# wiz55stm32.net
KiCad netlist of a schematic drawn in Altium Designer
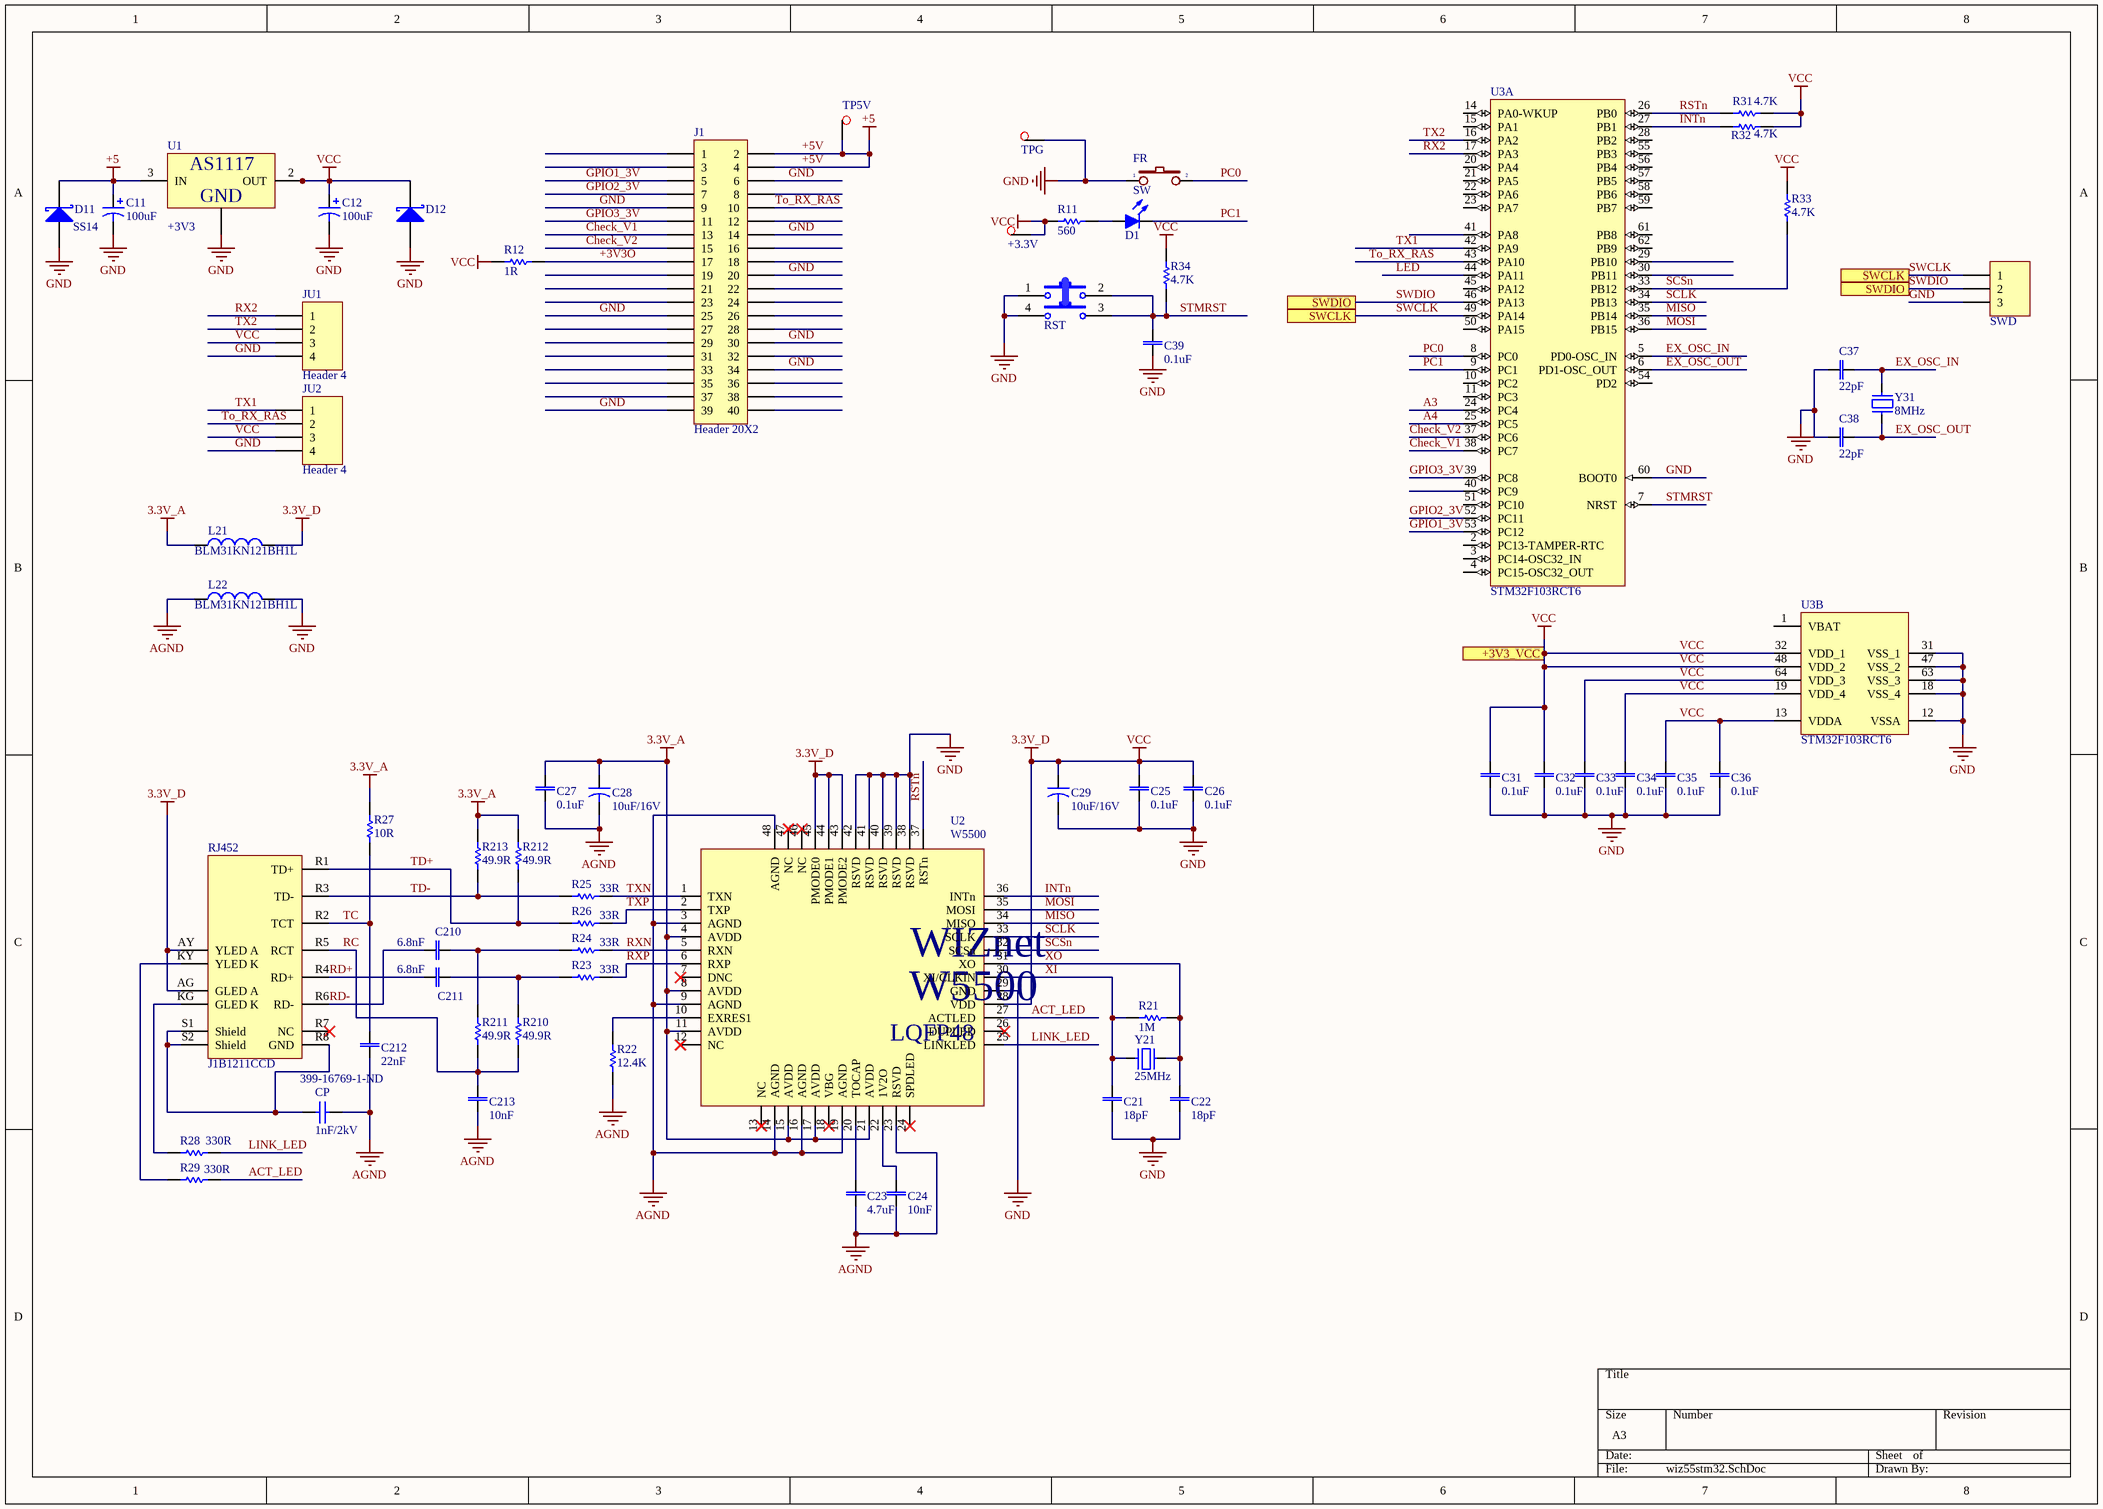
[diagram p0: wiz55stm32.SchDoc]

(export (version "E")
  (design (tool "Eeschema 10.0.6"))
  (components
    (comp (ref "+3.3V") (value "TP") (footprint "swatpcblib:TP2") (libsource (lib "swatpcblib") (part "TP")))
    (comp (ref "C11")
      (value "100uF")
      (footprint "CAP 3.8mm")
      (fields (field (name "Comment") "Cap"))
      (libsource (lib "swatpcblib") (part "Cap"))
    )
    (comp (ref "C12")
      (value "100uF")
      (footprint "CAP 3.8mm")
      (fields (field (name "Comment") "Cap"))
      (libsource (lib "swatpcblib") (part "Cap"))
    )
    (comp (ref "C21")
      (value "18pF")
      (footprint "swatpcblib:CAP 0805")
      (description "Capacitor non polarized")
      (fields (field (name "Comment") "Tụ điện dán 080518pF"))
      (libsource (lib "swatpcblib") (part "CAP NP"))
    )
    (comp (ref "C22")
      (value "18pF")
      (footprint "swatpcblib:CAP 0805")
      (description "Capacitor non polarized")
      (fields (field (name "Comment") "Tụ điện dán 080518pF"))
      (libsource (lib "swatpcblib") (part "CAP NP"))
    )
    (comp (ref "C23")
      (value "4.7uF")
      (footprint "swatpcblib:CAP 0805")
      (description "Capacitor non polarized")
      (fields (field (name "Comment") "Tụ điện dán 08054.7uF"))
      (libsource (lib "swatpcblib") (part "CAP NP"))
    )
    (comp (ref "C24")
      (value "10nF")
      (footprint "swatpcblib:CAP 0805")
      (description "Capacitor non polarized")
      (fields (field (name "Comment") "Tụ điện dán 080510nF"))
      (libsource (lib "swatpcblib") (part "CAP NP"))
    )
    (comp (ref "C25")
      (value "0.1uF")
      (footprint "swatpcblib:CAP 0805")
      (description "Capacitor non polarized")
      (fields (field (name "Comment") "Tụ điện dán 08050.1uF"))
      (libsource (lib "swatpcblib") (part "CAP NP"))
    )
    (comp (ref "C26")
      (value "0.1uF")
      (footprint "swatpcblib:CAP 0805")
      (description "Capacitor non polarized")
      (fields (field (name "Comment") "Tụ điện dán 08050.1uF"))
      (libsource (lib "swatpcblib") (part "CAP NP"))
    )
    (comp (ref "C27")
      (value "0.1uF")
      (footprint "swatpcblib:CAP 0805")
      (description "Capacitor non polarized")
      (fields (field (name "Comment") "Tụ điện dán 08050.1uF"))
      (libsource (lib "swatpcblib") (part "CAP NP"))
    )
    (comp (ref "C28")
      (value "10uF/16V")
      (footprint "CAP-A Size")
      (description "Tantla CAP A Size EIA/IECQ 3216")
      (libsource (lib "Scott_lib") (part "CAP-A Size"))
    )
    (comp (ref "C29")
      (value "10uF/16V")
      (footprint "CAP-A Size")
      (description "Tantla CAP A Size EIA/IECQ 3216")
      (libsource (lib "Scott_lib") (part "CAP-A Size"))
    )
    (comp (ref "C31")
      (value "0.1uF")
      (footprint "swatpcblib:CAP 0805")
      (description "Capacitor non polarized")
      (fields (field (name "Comment") "Tụ điện dán 08050.1uF"))
      (libsource (lib "swatpcblib") (part "CAP NP"))
    )
    (comp (ref "C32")
      (value "0.1uF")
      (footprint "swatpcblib:CAP 0805")
      (description "Capacitor non polarized")
      (fields (field (name "Comment") "Tụ điện dán 08050.1uF"))
      (libsource (lib "swatpcblib") (part "CAP NP"))
    )
    (comp (ref "C33")
      (value "0.1uF")
      (footprint "swatpcblib:CAP 0805")
      (description "Capacitor non polarized")
      (fields (field (name "Comment") "Tụ điện dán 08050.1uF"))
      (libsource (lib "swatpcblib") (part "CAP NP"))
    )
    (comp (ref "C34")
      (value "0.1uF")
      (footprint "swatpcblib:CAP 0805")
      (description "Capacitor non polarized")
      (fields (field (name "Comment") "Tụ điện dán 08050.1uF"))
      (libsource (lib "swatpcblib") (part "CAP NP"))
    )
    (comp (ref "C35")
      (value "0.1uF")
      (footprint "swatpcblib:CAP 0805")
      (description "Capacitor non polarized")
      (fields (field (name "Comment") "Tụ điện dán 08050.1uF"))
      (libsource (lib "swatpcblib") (part "CAP NP"))
    )
    (comp (ref "C36")
      (value "0.1uF")
      (footprint "swatpcblib:CAP 0805")
      (description "Capacitor non polarized")
      (fields (field (name "Comment") "Tụ điện dán 08050.1uF"))
      (libsource (lib "swatpcblib") (part "CAP NP"))
    )
    (comp (ref "C37")
      (value "22pF")
      (footprint "swatpcblib:CAP 0805")
      (description "Capacitor non polarized")
      (fields (field (name "Comment") "Tụ điện dán 080522pF"))
      (libsource (lib "swatpcblib") (part "CAP NP"))
    )
    (comp (ref "C38")
      (value "22pF")
      (footprint "swatpcblib:CAP 0805")
      (description "Capacitor non polarized")
      (fields (field (name "Comment") "Tụ điện dán 080522pF"))
      (libsource (lib "swatpcblib") (part "CAP NP"))
    )
    (comp (ref "C39")
      (value "0.1uF")
      (footprint "swatpcblib:CAP 0805")
      (description "Capacitor non polarized")
      (fields (field (name "Comment") "Tụ điện dán 08050.1uF"))
      (libsource (lib "swatpcblib") (part "CAP NP"))
    )
    (comp (ref "C210")
      (value "6.8nF")
      (footprint "swatpcblib:CAP 0805")
      (description "Capacitor non polarized")
      (fields (field (name "Comment") "Tụ điện dán 08056.8nF"))
      (libsource (lib "swatpcblib") (part "CAP NP"))
    )
    (comp (ref "C211")
      (value "6.8nF")
      (footprint "swatpcblib:CAP 0805")
      (description "Capacitor non polarized")
      (fields (field (name "Comment") "Tụ điện dán 08056.8nF"))
      (libsource (lib "swatpcblib") (part "CAP NP"))
    )
    (comp (ref "C212")
      (value "22nF")
      (footprint "swatpcblib:CAP 0805")
      (description "Capacitor non polarized")
      (fields (field (name "Comment") "Tụ điện dán 080522nF"))
      (libsource (lib "swatpcblib") (part "CAP NP"))
    )
    (comp (ref "C213")
      (value "10nF")
      (footprint "swatpcblib:CAP 0805")
      (description "Capacitor non polarized")
      (fields (field (name "Comment") "Tụ điện dán 080510nF"))
      (libsource (lib "swatpcblib") (part "CAP NP"))
    )
    (comp (ref "CP")
      (value "1nF/2kV")
      (footprint "CAP-1808")
      (description "Ceramic CAP 1808(4520)")
      (fields (field (name "SUPPLIER PART NUMBER 1") "399-16769-1-ND") (field (name "TOLERANCE") "20%"))
      (libsource (lib "Scott_lib") (part "CAP-1808"))
    )
    (comp (ref "D1") (value "Led") (footprint "LED 5mm Green") (libsource (lib "swatpcblib") (part "Led")))
    (comp (ref "D11")
      (value "SS14")
      (footprint "PBL - SMD Packages:DO-214AC")
      (description "Schottky Diodes Through Hole 3 A 40 V Schottky Diodes, DO-201AD, SB340 ,MBR340")
      (fields (field (name "Comment") "Đi ốt dánSS14"))
      (libsource (lib "swatpcblib") (part "Diodes Schottky"))
    )
    (comp (ref "D12")
      (value "Đi ốt dánPN:CPDH3V3UP")
      (footprint "swatpcblib:DO-35")
      (description "Zener 3.3V/1W")
      (libsource (lib "swatpcblib") (part "Diodes Schottky"))
    )
    (comp (ref "FR")
      (value "SW")
      (footprint "heromap:SW2-D1")
      (description "Switch button 2 pin")
      (libsource (lib "heromap") (part "SW2"))
    )
    (comp (ref "J1")
      (value "Header 20X2")
      (footprint "HDR2X20")
      (description "Header, 20-Pin, Dual row")
      (fields (field (name "PUBLISHER") "Altium Limited"))
      (libsource (lib "Miscellaneous Connectors") (part "Header 20X2"))
    )
    (comp (ref "JU1")
      (value "Header 4")
      (footprint "heromap:HDR1X4")
      (description "Header, 4-Pin")
      (fields (field (name "PUBLISHER") "Altium Limited"))
      (libsource (lib "heromap") (part "Header 4"))
    )
    (comp (ref "JU2")
      (value "Header 4")
      (footprint "heromap:HDR1X4")
      (description "Header, 4-Pin")
      (fields (field (name "PUBLISHER") "Altium Limited"))
      (libsource (lib "heromap") (part "Header 4"))
    )
    (comp (ref "L21")
      (value "BLM31KN121BH1L")
      (footprint "swatpcblib:SMD 1206")
      (description "Ferrite Beads 1206 120ohms 4A AEC-Q200")
      (libsource (lib "Scott_lib") (part "IND-0603"))
    )
    (comp (ref "L22")
      (value "BLM31KN121BH1L")
      (footprint "swatpcblib:SMD 1206")
      (description "Ferrite Beads 1206 120ohms 4A AEC-Q200")
      (libsource (lib "Scott_lib") (part "IND-0603"))
    )
    (comp (ref "R11")
      (value "560")
      (footprint "swatpcblib:RES 0805")
      (description "Resistor")
      (fields (field (name "Comment") "Điện trở dán 0603560"))
      (libsource (lib "swatpcblib") (part "Res"))
    )
    (comp (ref "R12")
      (value "1R")
      (footprint "swatpcblib:RES 0805")
      (description "Resistor")
      (fields (field (name "Comment") "Điện trở dán 08051R"))
      (libsource (lib "swatpcblib") (part "Res"))
    )
    (comp (ref "R21")
      (value "1M")
      (footprint "swatpcblib:RES 0805")
      (description "Resistor")
      (fields (field (name "Comment") "Điện trở dán 08051M"))
      (libsource (lib "swatpcblib") (part "Res"))
    )
    (comp (ref "R22")
      (value "12.4K")
      (footprint "swatpcblib:RES 0805")
      (description "Resistor")
      (fields (field (name "Comment") "Điện trở dán 080512.4K"))
      (libsource (lib "swatpcblib") (part "Res"))
    )
    (comp (ref "R23")
      (value "33R")
      (footprint "swatpcblib:RES 0805")
      (description "Resistor")
      (fields (field (name "Comment") "Điện trở dán 080533R"))
      (libsource (lib "swatpcblib") (part "Res"))
    )
    (comp (ref "R24")
      (value "33R")
      (footprint "swatpcblib:RES 0805")
      (description "Resistor")
      (fields (field (name "Comment") "Điện trở dán 080533R"))
      (libsource (lib "swatpcblib") (part "Res"))
    )
    (comp (ref "R25")
      (value "33R")
      (footprint "swatpcblib:RES 0805")
      (description "Resistor")
      (fields (field (name "Comment") "Điện trở dán 080533R"))
      (libsource (lib "swatpcblib") (part "Res"))
    )
    (comp (ref "R26")
      (value "33R")
      (footprint "swatpcblib:RES 0805")
      (description "Resistor")
      (fields (field (name "Comment") "Điện trở dán 080533R"))
      (libsource (lib "swatpcblib") (part "Res"))
    )
    (comp (ref "R27")
      (value "10R")
      (footprint "swatpcblib:RES 0805")
      (description "Resistor")
      (fields (field (name "Comment") "Điện trở dán 080510R"))
      (libsource (lib "swatpcblib") (part "Res"))
    )
    (comp (ref "R28")
      (value "330R")
      (footprint "swatpcblib:RES 0805")
      (description "Resistor")
      (fields (field (name "Comment") "Điện trở dán 0805330R"))
      (libsource (lib "swatpcblib") (part "Res"))
    )
    (comp (ref "R29")
      (value "330R")
      (footprint "swatpcblib:RES 0805")
      (description "Resistor")
      (fields (field (name "Comment") "Điện trở dán 0805330R"))
      (libsource (lib "swatpcblib") (part "Res"))
    )
    (comp (ref "R31")
      (value "4.7K")
      (footprint "swatpcblib:RES 0805")
      (description "Resistor")
      (fields (field (name "Comment") "Điện trở dán 08054.7K"))
      (libsource (lib "swatpcblib") (part "Res"))
    )
    (comp (ref "R32")
      (value "4.7K")
      (footprint "swatpcblib:RES 0805")
      (description "Resistor")
      (fields (field (name "Comment") "Điện trở dán 08054.7K"))
      (libsource (lib "swatpcblib") (part "Res"))
    )
    (comp (ref "R33")
      (value "4.7K")
      (footprint "swatpcblib:RES 0805")
      (description "Resistor")
      (fields (field (name "Comment") "Điện trở dán 08054.7K"))
      (libsource (lib "swatpcblib") (part "Res"))
    )
    (comp (ref "R34")
      (value "4.7K")
      (footprint "swatpcblib:RES 0805")
      (description "Resistor")
      (fields (field (name "Comment") "Điện trở dán 08054.7K"))
      (libsource (lib "swatpcblib") (part "Res"))
    )
    (comp (ref "R210")
      (value "49.9R")
      (footprint "swatpcblib:RES 0805")
      (description "Resistor")
      (fields (field (name "Comment") "Điện trở dán 080549.9R"))
      (libsource (lib "swatpcblib") (part "Res"))
    )
    (comp (ref "R211")
      (value "49.9R")
      (footprint "swatpcblib:RES 0805")
      (description "Resistor")
      (fields (field (name "Comment") "Điện trở dán 080549.9R"))
      (libsource (lib "swatpcblib") (part "Res"))
    )
    (comp (ref "R212")
      (value "49.9R")
      (footprint "swatpcblib:RES 0805")
      (description "Resistor")
      (fields (field (name "Comment") "Điện trở dán 080549.9R"))
      (libsource (lib "swatpcblib") (part "Res"))
    )
    (comp (ref "R213")
      (value "49.9R")
      (footprint "swatpcblib:RES 0805")
      (description "Resistor")
      (fields (field (name "Comment") "Điện trở dán 080549.9R"))
      (libsource (lib "swatpcblib") (part "Res"))
    )
    (comp (ref "RJ452")
      (value "J1B1211CCD")
      (footprint "swatpcblib:J1B1211CCD")
      (libsource (lib "WIZ850io_SCH_V100") (part "BS-R250210"))
    )
    (comp (ref "RST")
      (value "Nút bấm 4 chân cắm12x12x6mm")
      (footprint "SW")
      (libsource (lib "swatpcblib") (part "SW-4P-Small"))
    )
    (comp (ref "SWD")
      (value "Header 3")
      (footprint "heromap:HDR1X3")
      (description "Header, 3-Pin")
      (fields (field (name "PUBLISHER") "Altium Limited"))
      (libsource (lib "heromap") (part "Header 3"))
    )
    (comp (ref "TP5V") (value "TP") (footprint "swatpcblib:TP2") (libsource (lib "swatpcblib") (part "TP")))
    (comp (ref "TPG") (value "TP") (footprint "swatpcblib:TP2") (libsource (lib "swatpcblib") (part "TP")))
    (comp (ref "U1")
      (value "IC nguồn AS1117 dán+3V3")
      (footprint "SOT223-4N")
      (fields (field (name "VL") "+3V3"))
      (libsource (lib "swatpcblib") (part "AS1117"))
    )
    (comp (ref "U2")
      (value "W5500")
      (footprint "WIZnet W5500")
      (description "WIZnet W5500")
      (libsource (lib "WIZnet Open-source Hardware Library V1.0") (part "W5500"))
    )
    (comp (ref "U3")
      (value "STM32F103RCT6")
      (footprint "LQFP64_Tuan")
      (libsource (lib "STMicroelectronics STM32 F1") (part "STM32F103RCT6"))
    )
    (comp (ref "Y21") (value "25MHz") (footprint "XT2") (libsource (lib "swatpcblib") (part "Crystal")))
    (comp (ref "Y31") (value "8MHz") (footprint "XT2") (libsource (lib "Tuan") (part "Crystal")))
  )
  (nets
    (net (code "1") (name "+5") (class "Default")
      (node (ref "C11") (pin "1") (pinfunction "1_1") (pintype "passive"))
      (node (ref "D11") (pin "K") (pinfunction "K_K") (pintype "passive"))
      (node (ref "J1") (pin "2") (pinfunction "2_2") (pintype "passive"))
      (node (ref "J1") (pin "4") (pinfunction "4_4") (pintype "passive"))
      (node (ref "TP5V") (pin "1") (pinfunction "1_1") (pintype "passive"))
      (node (ref "U1") (pin "3") (pinfunction "IN_3") (pintype "power_in"))
    )
    (net (code "2") (name "/+3V3O") (class "Default")
      (node (ref "J1") (pin "17") (pinfunction "17_17") (pintype "passive"))
      (node (ref "R12") (pin "2") (pinfunction "2_2") (pintype "passive"))
    )
    (net (code "3") (name "/A3") (class "Default")
      (node (ref "U3") (pin "24") (pinfunction "PC4_24") (pintype "bidirectional"))
    )
    (net (code "4") (name "/A4") (class "Default")
      (node (ref "U3") (pin "25") (pinfunction "PC5_25") (pintype "bidirectional"))
    )
    (net (code "5") (name "/ACT_LED") (class "Default")
      (node (ref "R29") (pin "2") (pinfunction "2_2") (pintype "passive"))
      (node (ref "U2") (pin "27") (pinfunction "ACTLED_27") (pintype "passive"))
    )
    (net (code "6") (name "/Check_V1") (class "Default")
      (node (ref "J1") (pin "13") (pinfunction "13_13") (pintype "passive"))
      (node (ref "U3") (pin "38") (pinfunction "PC7_38") (pintype "bidirectional"))
    )
    (net (code "7") (name "/Check_V2") (class "Default")
      (node (ref "J1") (pin "15") (pinfunction "15_15") (pintype "passive"))
      (node (ref "U3") (pin "37") (pinfunction "PC6_37") (pintype "bidirectional"))
    )
    (net (code "8") (name "/EX_OSC_IN") (class "Default")
      (node (ref "C37") (pin "1") (pinfunction "1_1") (pintype "passive"))
      (node (ref "U3") (pin "5") (pinfunction "PD0-OSC_IN_5") (pintype "bidirectional"))
      (node (ref "Y31") (pin "2") (pinfunction "2_2") (pintype "passive"))
    )
    (net (code "9") (name "/EX_OSC_OUT") (class "Default")
      (node (ref "C38") (pin "1") (pinfunction "1_1") (pintype "passive"))
      (node (ref "U3") (pin "6") (pinfunction "PD1-OSC_OUT_6") (pintype "bidirectional"))
      (node (ref "Y31") (pin "1") (pinfunction "1_1") (pintype "passive"))
    )
    (net (code "10") (name "/GPIO1_3V") (class "Default")
      (node (ref "J1") (pin "5") (pinfunction "5_5") (pintype "passive"))
      (node (ref "U3") (pin "53") (pinfunction "PC12_53") (pintype "bidirectional"))
    )
    (net (code "11") (name "/GPIO2_3V") (class "Default")
      (node (ref "J1") (pin "7") (pinfunction "7_7") (pintype "passive"))
      (node (ref "U3") (pin "52") (pinfunction "PC11_52") (pintype "bidirectional"))
    )
    (net (code "12") (name "/GPIO3_3V") (class "Default")
      (node (ref "J1") (pin "11") (pinfunction "11_11") (pintype "passive"))
      (node (ref "U3") (pin "39") (pinfunction "PC8_39") (pintype "bidirectional"))
    )
    (net (code "13") (name "/INTn") (class "Default")
      (node (ref "R32") (pin "2") (pinfunction "2_2") (pintype "passive"))
      (node (ref "U2") (pin "36") (pinfunction "INTn_36") (pintype "passive"))
      (node (ref "U3") (pin "27") (pinfunction "PB1_27") (pintype "bidirectional"))
    )
    (net (code "14") (name "/LED") (class "Default")
      (node (ref "U3") (pin "44") (pinfunction "PA11_44") (pintype "bidirectional"))
    )
    (net (code "15") (name "/LINK_LED") (class "Default")
      (node (ref "R28") (pin "2") (pinfunction "2_2") (pintype "passive"))
      (node (ref "U2") (pin "25") (pinfunction "LINKLED_25") (pintype "passive"))
    )
    (net (code "16") (name "/MISO") (class "Default")
      (node (ref "U2") (pin "34") (pinfunction "MISO_34") (pintype "passive"))
      (node (ref "U3") (pin "35") (pinfunction "PB14_35") (pintype "bidirectional"))
    )
    (net (code "17") (name "/MOSI") (class "Default")
      (node (ref "U2") (pin "35") (pinfunction "MOSI_35") (pintype "passive"))
      (node (ref "U3") (pin "36") (pinfunction "PB15_36") (pintype "bidirectional"))
    )
    (net (code "18") (name "/PC0") (class "Default")
      (node (ref "FR") (pin "2") (pinfunction "2_2") (pintype "passive"))
      (node (ref "U3") (pin "8") (pinfunction "PC0_8") (pintype "bidirectional"))
    )
    (net (code "19") (name "/PC1") (class "Default")
      (node (ref "D1") (pin "K") (pinfunction "K_K") (pintype "passive"))
      (node (ref "U3") (pin "9") (pinfunction "PC1_9") (pintype "bidirectional"))
    )
    (net (code "20") (name "/RC") (class "Default")
      (node (ref "C213") (pin "1") (pinfunction "1_1") (pintype "passive"))
      (node (ref "R210") (pin "1") (pinfunction "1_1") (pintype "passive"))
      (node (ref "R211") (pin "1") (pinfunction "1_1") (pintype "passive"))
      (node (ref "RJ452") (pin "R5") (pinfunction "RCT_R5") (pintype "passive"))
    )
    (net (code "21") (name "/RD+") (class "Default")
      (node (ref "C211") (pin "2") (pinfunction "2_2") (pintype "passive"))
      (node (ref "RJ452") (pin "R4") (pinfunction "RD+_R4") (pintype "passive"))
    )
    (net (code "22") (name "/RD-") (class "Default")
      (node (ref "C210") (pin "2") (pinfunction "2_2") (pintype "passive"))
      (node (ref "RJ452") (pin "R6") (pinfunction "RD-_R6") (pintype "passive"))
    )
    (net (code "23") (name "/RSTn") (class "Default")
      (node (ref "R31") (pin "2") (pinfunction "2_2") (pintype "passive"))
      (node (ref "U2") (pin "37") (pinfunction "RSTn_37") (pintype "passive"))
      (node (ref "U3") (pin "26") (pinfunction "PB0_26") (pintype "bidirectional"))
    )
    (net (code "24") (name "/RX2") (class "Default")
      (node (ref "JU1") (pin "1") (pinfunction "1_1") (pintype "passive"))
      (node (ref "U3") (pin "17") (pinfunction "PA3_17") (pintype "bidirectional"))
    )
    (net (code "25") (name "/RXN") (class "Default")
      (node (ref "R24") (pin "1") (pinfunction "1_1") (pintype "passive"))
      (node (ref "U2") (pin "5") (pinfunction "RXN_5") (pintype "passive"))
    )
    (net (code "26") (name "/RXP") (class "Default")
      (node (ref "R23") (pin "1") (pinfunction "1_1") (pintype "passive"))
      (node (ref "U2") (pin "6") (pinfunction "RXP_6") (pintype "passive"))
    )
    (net (code "27") (name "/SCLK") (class "Default")
      (node (ref "U2") (pin "33") (pinfunction "SCLK_33") (pintype "passive"))
      (node (ref "U3") (pin "34") (pinfunction "PB13_34") (pintype "bidirectional"))
    )
    (net (code "28") (name "/SCSn") (class "Default")
      (node (ref "R33") (pin "1") (pinfunction "1_1") (pintype "passive"))
      (node (ref "U2") (pin "32") (pinfunction "SCSn_32") (pintype "passive"))
      (node (ref "U3") (pin "33") (pinfunction "PB12_33") (pintype "bidirectional"))
    )
    (net (code "29") (name "/STMRST") (class "Default")
      (node (ref "C39") (pin "2") (pinfunction "2_2") (pintype "passive"))
      (node (ref "R34") (pin "1") (pinfunction "1_1") (pintype "passive"))
      (node (ref "RST") (pin "2") (pinfunction "2_2") (pintype "passive"))
      (node (ref "RST") (pin "3") (pinfunction "3_3") (pintype "passive"))
      (node (ref "U3") (pin "7") (pinfunction "NRST_7") (pintype "bidirectional"))
    )
    (net (code "30") (name "/SWCLK") (class "Default")
      (node (ref "SWD") (pin "1") (pinfunction "1_1") (pintype "passive"))
      (node (ref "U3") (pin "49") (pinfunction "PA14_49") (pintype "bidirectional"))
    )
    (net (code "31") (name "/SWDIO") (class "Default")
      (node (ref "SWD") (pin "2") (pinfunction "2_2") (pintype "passive"))
      (node (ref "U3") (pin "46") (pinfunction "PA13_46") (pintype "bidirectional"))
    )
    (net (code "32") (name "/TC") (class "Default")
      (node (ref "C212") (pin "1") (pinfunction "1_1") (pintype "passive"))
      (node (ref "R27") (pin "2") (pinfunction "2_2") (pintype "passive"))
      (node (ref "RJ452") (pin "R2") (pinfunction "TCT_R2") (pintype "passive"))
    )
    (net (code "33") (name "/TD+") (class "Default")
      (node (ref "R212") (pin "1") (pinfunction "1_1") (pintype "passive"))
      (node (ref "R26") (pin "2") (pinfunction "2_2") (pintype "passive"))
      (node (ref "RJ452") (pin "R1") (pinfunction "TD+_R1") (pintype "passive"))
    )
    (net (code "34") (name "/TD-") (class "Default")
      (node (ref "R213") (pin "1") (pinfunction "1_1") (pintype "passive"))
      (node (ref "R25") (pin "2") (pinfunction "2_2") (pintype "passive"))
      (node (ref "RJ452") (pin "R3") (pinfunction "TD-_R3") (pintype "passive"))
    )
    (net (code "35") (name "/TX1") (class "Default")
      (node (ref "JU2") (pin "1") (pinfunction "1_1") (pintype "passive"))
      (node (ref "U3") (pin "42") (pinfunction "PA9_42") (pintype "bidirectional"))
    )
    (net (code "36") (name "/TX2") (class "Default")
      (node (ref "JU1") (pin "2") (pinfunction "2_2") (pintype "passive"))
      (node (ref "U3") (pin "16") (pinfunction "PA2_16") (pintype "bidirectional"))
    )
    (net (code "37") (name "/TXN") (class "Default")
      (node (ref "R25") (pin "1") (pinfunction "1_1") (pintype "passive"))
      (node (ref "U2") (pin "1") (pinfunction "TXN_1") (pintype "passive"))
    )
    (net (code "38") (name "/TXP") (class "Default")
      (node (ref "R26") (pin "1") (pinfunction "1_1") (pintype "passive"))
      (node (ref "U2") (pin "2") (pinfunction "TXP_2") (pintype "passive"))
    )
    (net (code "39") (name "/To_RX_RAS") (class "Default")
      (node (ref "J1") (pin "10") (pinfunction "10_10") (pintype "passive"))
      (node (ref "JU2") (pin "2") (pinfunction "2_2") (pintype "passive"))
      (node (ref "U3") (pin "43") (pinfunction "PA10_43") (pintype "bidirectional"))
    )
    (net (code "40") (name "/XI") (class "Default")
      (node (ref "C21") (pin "2") (pinfunction "2_2") (pintype "passive"))
      (node (ref "R21") (pin "1") (pinfunction "1_1") (pintype "passive"))
      (node (ref "U2") (pin "30") (pinfunction "XI/CLKIN_30") (pintype "passive"))
      (node (ref "Y21") (pin "1") (pinfunction "1_1") (pintype "passive"))
    )
    (net (code "41") (name "/XO") (class "Default")
      (node (ref "C22") (pin "2") (pinfunction "2_2") (pintype "passive"))
      (node (ref "R21") (pin "2") (pinfunction "2_2") (pintype "passive"))
      (node (ref "U2") (pin "31") (pinfunction "XO_31") (pintype "passive"))
      (node (ref "Y21") (pin "2") (pinfunction "2_2") (pintype "passive"))
    )
    (net (code "42") (name "3.3V_A") (class "Default")
      (node (ref "C27") (pin "2") (pinfunction "2_2") (pintype "passive"))
      (node (ref "C28") (pin "1") (pinfunction "1_1") (pintype "passive"))
      (node (ref "L21") (pin "1") (pinfunction "1_1") (pintype "passive"))
      (node (ref "R212") (pin "2") (pinfunction "2_2") (pintype "passive"))
      (node (ref "R213") (pin "2") (pinfunction "2_2") (pintype "passive"))
      (node (ref "R27") (pin "1") (pinfunction "1_1") (pintype "passive"))
      (node (ref "U2") (pin "11") (pinfunction "AVDD_11") (pintype "passive"))
      (node (ref "U2") (pin "15") (pinfunction "AVDD_15") (pintype "passive"))
      (node (ref "U2") (pin "17") (pinfunction "AVDD_17") (pintype "passive"))
      (node (ref "U2") (pin "21") (pinfunction "AVDD_21") (pintype "passive"))
      (node (ref "U2") (pin "4") (pinfunction "AVDD_4") (pintype "passive"))
      (node (ref "U2") (pin "8") (pinfunction "AVDD_8") (pintype "passive"))
    )
    (net (code "43") (name "3.3V_D") (class "Default")
      (node (ref "+3.3V") (pin "1") (pinfunction "1_1") (pintype "passive"))
      (node (ref "C12") (pin "1") (pinfunction "1_1") (pintype "passive"))
      (node (ref "C25") (pin "2") (pinfunction "2_2") (pintype "passive"))
      (node (ref "C26") (pin "2") (pinfunction "2_2") (pintype "passive"))
      (node (ref "C29") (pin "1") (pinfunction "1_1") (pintype "passive"))
      (node (ref "C31") (pin "2") (pinfunction "2_2") (pintype "passive"))
      (node (ref "C32") (pin "2") (pinfunction "2_2") (pintype "passive"))
      (node (ref "C33") (pin "2") (pinfunction "2_2") (pintype "passive"))
      (node (ref "C34") (pin "2") (pinfunction "2_2") (pintype "passive"))
      (node (ref "C35") (pin "2") (pinfunction "2_2") (pintype "passive"))
      (node (ref "C36") (pin "2") (pinfunction "2_2") (pintype "passive"))
      (node (ref "D12") (pin "K") (pinfunction "K_K") (pintype "passive"))
      (node (ref "JU1") (pin "3") (pinfunction "3_3") (pintype "passive"))
      (node (ref "JU2") (pin "3") (pinfunction "3_3") (pintype "passive"))
      (node (ref "L21") (pin "2") (pinfunction "2_2") (pintype "passive"))
      (node (ref "R11") (pin "1") (pinfunction "1_1") (pintype "passive"))
      (node (ref "R12") (pin "1") (pinfunction "1_1") (pintype "passive"))
      (node (ref "R31") (pin "1") (pinfunction "1_1") (pintype "passive"))
      (node (ref "R32") (pin "1") (pinfunction "1_1") (pintype "passive"))
      (node (ref "R33") (pin "2") (pinfunction "2_2") (pintype "passive"))
      (node (ref "R34") (pin "2") (pinfunction "2_2") (pintype "passive"))
      (node (ref "RJ452") (pin "AG") (pinfunction "GLED_A_AG") (pintype "passive"))
      (node (ref "RJ452") (pin "AY") (pinfunction "YLED_A_AY") (pintype "passive"))
      (node (ref "U1") (pin "2") (pinfunction "OUT_2") (pintype "power_in"))
      (node (ref "U1") (pin "4") (pinfunction "4_4") (pintype "passive"))
      (node (ref "U2") (pin "28") (pinfunction "VDD_28") (pintype "passive"))
      (node (ref "U2") (pin "43") (pinfunction "PMODE2_43") (pintype "passive"))
      (node (ref "U2") (pin "44") (pinfunction "PMODE1_44") (pintype "passive"))
      (node (ref "U2") (pin "45") (pinfunction "PMODE0_45") (pintype "passive"))
      (node (ref "U3") (pin "13") (pinfunction "VDDA_13") (pintype "power_in"))
      (node (ref "U3") (pin "19") (pinfunction "VDD_4_19") (pintype "power_in"))
      (node (ref "U3") (pin "32") (pinfunction "VDD_1_32") (pintype "power_in"))
      (node (ref "U3") (pin "48") (pinfunction "VDD_2_48") (pintype "power_in"))
      (node (ref "U3") (pin "64") (pinfunction "VDD_3_64") (pintype "power_in"))
    )
    (net (code "44") (name "AGND") (class "Default")
      (node (ref "C212") (pin "2") (pinfunction "2_2") (pintype "passive"))
      (node (ref "C213") (pin "2") (pinfunction "2_2") (pintype "passive"))
      (node (ref "C23") (pin "1") (pinfunction "1_1") (pintype "passive"))
      (node (ref "C24") (pin "1") (pinfunction "1_1") (pintype "passive"))
      (node (ref "C27") (pin "1") (pinfunction "1_1") (pintype "passive"))
      (node (ref "C28") (pin "2") (pinfunction "2_2") (pintype "passive"))
      (node (ref "CP") (pin "1") (pinfunction "1_1") (pintype "passive"))
      (node (ref "L22") (pin "1") (pinfunction "1_1") (pintype "passive"))
      (node (ref "R22") (pin "1") (pinfunction "1_1") (pintype "passive"))
      (node (ref "U2") (pin "14") (pinfunction "AGND_14") (pintype "passive"))
      (node (ref "U2") (pin "16") (pinfunction "AGND_16") (pintype "passive"))
      (node (ref "U2") (pin "19") (pinfunction "AGND_19") (pintype "passive"))
      (node (ref "U2") (pin "23") (pinfunction "RSVD_23") (pintype "passive"))
      (node (ref "U2") (pin "3") (pinfunction "AGND_3") (pintype "passive"))
      (node (ref "U2") (pin "48") (pinfunction "AGND_48") (pintype "passive"))
      (node (ref "U2") (pin "9") (pinfunction "AGND_9") (pintype "passive"))
    )
    (net (code "45") (name "GND") (class "Default")
      (node (ref "C11") (pin "2") (pinfunction "2_2") (pintype "passive"))
      (node (ref "C12") (pin "2") (pinfunction "2_2") (pintype "passive"))
      (node (ref "C21") (pin "1") (pinfunction "1_1") (pintype "passive"))
      (node (ref "C22") (pin "1") (pinfunction "1_1") (pintype "passive"))
      (node (ref "C25") (pin "1") (pinfunction "1_1") (pintype "passive"))
      (node (ref "C26") (pin "1") (pinfunction "1_1") (pintype "passive"))
      (node (ref "C29") (pin "2") (pinfunction "2_2") (pintype "passive"))
      (node (ref "C31") (pin "1") (pinfunction "1_1") (pintype "passive"))
      (node (ref "C32") (pin "1") (pinfunction "1_1") (pintype "passive"))
      (node (ref "C33") (pin "1") (pinfunction "1_1") (pintype "passive"))
      (node (ref "C34") (pin "1") (pinfunction "1_1") (pintype "passive"))
      (node (ref "C35") (pin "1") (pinfunction "1_1") (pintype "passive"))
      (node (ref "C36") (pin "1") (pinfunction "1_1") (pintype "passive"))
      (node (ref "C37") (pin "2") (pinfunction "2_2") (pintype "passive"))
      (node (ref "C38") (pin "2") (pinfunction "2_2") (pintype "passive"))
      (node (ref "C39") (pin "1") (pinfunction "1_1") (pintype "passive"))
      (node (ref "D11") (pin "A") (pinfunction "A_A") (pintype "passive"))
      (node (ref "D12") (pin "A") (pinfunction "A_A") (pintype "passive"))
      (node (ref "FR") (pin "1") (pinfunction "1_1") (pintype "passive"))
      (node (ref "J1") (pin "14") (pinfunction "14_14") (pintype "passive"))
      (node (ref "J1") (pin "20") (pinfunction "20_20") (pintype "passive"))
      (node (ref "J1") (pin "25") (pinfunction "25_25") (pintype "passive"))
      (node (ref "J1") (pin "30") (pinfunction "30_30") (pintype "passive"))
      (node (ref "J1") (pin "34") (pinfunction "34_34") (pintype "passive"))
      (node (ref "J1") (pin "39") (pinfunction "39_39") (pintype "passive"))
      (node (ref "J1") (pin "6") (pinfunction "6_6") (pintype "passive"))
      (node (ref "J1") (pin "9") (pinfunction "9_9") (pintype "passive"))
      (node (ref "JU1") (pin "4") (pinfunction "4_4") (pintype "passive"))
      (node (ref "JU2") (pin "4") (pinfunction "4_4") (pintype "passive"))
      (node (ref "L22") (pin "2") (pinfunction "2_2") (pintype "passive"))
      (node (ref "RST") (pin "1") (pinfunction "1_1") (pintype "passive"))
      (node (ref "RST") (pin "4") (pinfunction "4_4") (pintype "passive"))
      (node (ref "SWD") (pin "3") (pinfunction "3_3") (pintype "passive"))
      (node (ref "TPG") (pin "1") (pinfunction "1_1") (pintype "passive"))
      (node (ref "U1") (pin "1") (pinfunction "GND_1") (pintype "power_in"))
      (node (ref "U2") (pin "29") (pinfunction "GND_29") (pintype "passive"))
      (node (ref "U2") (pin "38") (pinfunction "RSVD_38") (pintype "passive"))
      (node (ref "U2") (pin "39") (pinfunction "RSVD_39") (pintype "passive"))
      (node (ref "U2") (pin "40") (pinfunction "RSVD_40") (pintype "passive"))
      (node (ref "U2") (pin "41") (pinfunction "RSVD_41") (pintype "passive"))
      (node (ref "U2") (pin "42") (pinfunction "RSVD_42") (pintype "passive"))
      (node (ref "U3") (pin "12") (pinfunction "VSSA_12") (pintype "power_in"))
      (node (ref "U3") (pin "18") (pinfunction "VSS_4_18") (pintype "power_in"))
      (node (ref "U3") (pin "31") (pinfunction "VSS_1_31") (pintype "power_in"))
      (node (ref "U3") (pin "47") (pinfunction "VSS_2_47") (pintype "power_in"))
      (node (ref "U3") (pin "60") (pinfunction "BOOT0_60") (pintype "input"))
      (node (ref "U3") (pin "63") (pinfunction "VSS_3_63") (pintype "power_in"))
    )
    (net (code "46") (name "Net-(C210-Pad1)") (class "Default")
      (node (ref "C210") (pin "1") (pinfunction "1_1") (pintype "passive"))
      (node (ref "R211") (pin "2") (pinfunction "2_2") (pintype "passive"))
      (node (ref "R24") (pin "2") (pinfunction "2_2") (pintype "passive"))
    )
    (net (code "47") (name "Net-(C211-Pad1)") (class "Default")
      (node (ref "C211") (pin "1") (pinfunction "1_1") (pintype "passive"))
      (node (ref "R210") (pin "2") (pinfunction "2_2") (pintype "passive"))
      (node (ref "R23") (pin "2") (pinfunction "2_2") (pintype "passive"))
    )
    (net (code "48") (name "Net-(D1-PadA)") (class "Default")
      (node (ref "D1") (pin "A") (pinfunction "A_A") (pintype "passive"))
      (node (ref "R11") (pin "2") (pinfunction "2_2") (pintype "passive"))
    )
    (net (code "49") (name "Net-(RJ452-GLED_K)") (class "Default")
      (node (ref "R28") (pin "1") (pinfunction "1_1") (pintype "passive"))
      (node (ref "RJ452") (pin "KG") (pinfunction "GLED_K_KG") (pintype "passive"))
    )
    (net (code "50") (name "Net-(RJ452-GND)") (class "Default")
      (node (ref "CP") (pin "2") (pinfunction "2_2") (pintype "passive"))
      (node (ref "RJ452") (pin "R8") (pinfunction "GND_R8") (pintype "passive"))
      (node (ref "RJ452") (pin "S1") (pinfunction "Shield_S1") (pintype "passive"))
      (node (ref "RJ452") (pin "S2") (pinfunction "Shield_S2") (pintype "passive"))
    )
    (net (code "51") (name "Net-(RJ452-YLED_K)") (class "Default")
      (node (ref "R29") (pin "1") (pinfunction "1_1") (pintype "passive"))
      (node (ref "RJ452") (pin "KY") (pinfunction "YLED_K_KY") (pintype "passive"))
    )
    (net (code "52") (name "Net-(U2-1V2O)") (class "Default")
      (node (ref "C24") (pin "2") (pinfunction "2_2") (pintype "passive"))
      (node (ref "U2") (pin "22") (pinfunction "1V2O_22") (pintype "passive"))
    )
    (net (code "53") (name "Net-(U2-EXRES1)") (class "Default")
      (node (ref "R22") (pin "2") (pinfunction "2_2") (pintype "passive"))
      (node (ref "U2") (pin "10") (pinfunction "EXRES1_10") (pintype "passive"))
    )
    (net (code "54") (name "Net-(U2-TOCAP)") (class "Default")
      (node (ref "C23") (pin "2") (pinfunction "2_2") (pintype "passive"))
      (node (ref "U2") (pin "20") (pinfunction "TOCAP_20") (pintype "passive"))
    )
    (net (code "55") (name "unconnected-(J1-Pad1)") (class "Default")
      (node (ref "J1") (pin "1") (pinfunction "1_1") (pintype "passive"))
    )
    (net (code "56") (name "unconnected-(J1-Pad3)") (class "Default")
      (node (ref "J1") (pin "3") (pinfunction "3_3") (pintype "passive"))
    )
    (net (code "57") (name "unconnected-(J1-Pad8)") (class "Default")
      (node (ref "J1") (pin "8") (pinfunction "8_8") (pintype "passive"))
    )
    (net (code "58") (name "unconnected-(J1-Pad12)") (class "Default")
      (node (ref "J1") (pin "12") (pinfunction "12_12") (pintype "passive"))
    )
    (net (code "59") (name "unconnected-(J1-Pad16)") (class "Default")
      (node (ref "J1") (pin "16") (pinfunction "16_16") (pintype "passive"))
    )
    (net (code "60") (name "unconnected-(J1-Pad18)") (class "Default")
      (node (ref "J1") (pin "18") (pinfunction "18_18") (pintype "passive"))
    )
    (net (code "61") (name "unconnected-(J1-Pad19)") (class "Default")
      (node (ref "J1") (pin "19") (pinfunction "19_19") (pintype "passive"))
    )
    (net (code "62") (name "unconnected-(J1-Pad21)") (class "Default")
      (node (ref "J1") (pin "21") (pinfunction "21_21") (pintype "passive"))
    )
    (net (code "63") (name "unconnected-(J1-Pad22)") (class "Default")
      (node (ref "J1") (pin "22") (pinfunction "22_22") (pintype "passive"))
    )
    (net (code "64") (name "unconnected-(J1-Pad23)") (class "Default")
      (node (ref "J1") (pin "23") (pinfunction "23_23") (pintype "passive"))
    )
    (net (code "65") (name "unconnected-(J1-Pad24)") (class "Default")
      (node (ref "J1") (pin "24") (pinfunction "24_24") (pintype "passive"))
    )
    (net (code "66") (name "unconnected-(J1-Pad26)") (class "Default")
      (node (ref "J1") (pin "26") (pinfunction "26_26") (pintype "passive"))
    )
    (net (code "67") (name "unconnected-(J1-Pad27)") (class "Default")
      (node (ref "J1") (pin "27") (pinfunction "27_27") (pintype "passive"))
    )
    (net (code "68") (name "unconnected-(J1-Pad28)") (class "Default")
      (node (ref "J1") (pin "28") (pinfunction "28_28") (pintype "passive"))
    )
    (net (code "69") (name "unconnected-(J1-Pad29)") (class "Default")
      (node (ref "J1") (pin "29") (pinfunction "29_29") (pintype "passive"))
    )
    (net (code "70") (name "unconnected-(J1-Pad31)") (class "Default")
      (node (ref "J1") (pin "31") (pinfunction "31_31") (pintype "passive"))
    )
    (net (code "71") (name "unconnected-(J1-Pad32)") (class "Default")
      (node (ref "J1") (pin "32") (pinfunction "32_32") (pintype "passive"))
    )
    (net (code "72") (name "unconnected-(J1-Pad33)") (class "Default")
      (node (ref "J1") (pin "33") (pinfunction "33_33") (pintype "passive"))
    )
    (net (code "73") (name "unconnected-(J1-Pad35)") (class "Default")
      (node (ref "J1") (pin "35") (pinfunction "35_35") (pintype "passive"))
    )
    (net (code "74") (name "unconnected-(J1-Pad36)") (class "Default")
      (node (ref "J1") (pin "36") (pinfunction "36_36") (pintype "passive"))
    )
    (net (code "75") (name "unconnected-(J1-Pad37)") (class "Default")
      (node (ref "J1") (pin "37") (pinfunction "37_37") (pintype "passive"))
    )
    (net (code "76") (name "unconnected-(J1-Pad38)") (class "Default")
      (node (ref "J1") (pin "38") (pinfunction "38_38") (pintype "passive"))
    )
    (net (code "77") (name "unconnected-(J1-Pad40)") (class "Default")
      (node (ref "J1") (pin "40") (pinfunction "40_40") (pintype "passive"))
    )
    (net (code "78") (name "unconnected-(RJ452-NC-PadR7)") (class "Default")
      (node (ref "RJ452") (pin "R7") (pinfunction "NC_R7") (pintype "passive+no_connect"))
    )
    (net (code "79") (name "unconnected-(U2-DNC-Pad7)") (class "Default")
      (node (ref "U2") (pin "7") (pinfunction "DNC_7") (pintype "passive+no_connect"))
    )
    (net (code "80") (name "unconnected-(U2-DUPLED-Pad26)") (class "Default")
      (node (ref "U2") (pin "26") (pinfunction "DUPLED_26") (pintype "passive+no_connect"))
    )
    (net (code "81") (name "unconnected-(U2-NC-Pad12)") (class "Default")
      (node (ref "U2") (pin "12") (pinfunction "NC_12") (pintype "passive+no_connect"))
    )
    (net (code "82") (name "unconnected-(U2-NC-Pad13)") (class "Default")
      (node (ref "U2") (pin "13") (pinfunction "NC_13") (pintype "passive+no_connect"))
    )
    (net (code "83") (name "unconnected-(U2-NC-Pad46)") (class "Default")
      (node (ref "U2") (pin "46") (pinfunction "NC_46") (pintype "passive+no_connect"))
    )
    (net (code "84") (name "unconnected-(U2-NC-Pad47)") (class "Default")
      (node (ref "U2") (pin "47") (pinfunction "NC_47") (pintype "passive+no_connect"))
    )
    (net (code "85") (name "unconnected-(U2-SPDLED-Pad24)") (class "Default")
      (node (ref "U2") (pin "24") (pinfunction "SPDLED_24") (pintype "passive+no_connect"))
    )
    (net (code "86") (name "unconnected-(U2-VBG-Pad18)") (class "Default")
      (node (ref "U2") (pin "18") (pinfunction "VBG_18") (pintype "passive+no_connect"))
    )
    (net (code "87") (name "unconnected-(U3A-PA0-WKUP-Pad14)") (class "Default")
      (node (ref "U3") (pin "14") (pinfunction "PA0-WKUP_14") (pintype "bidirectional"))
    )
    (net (code "88") (name "unconnected-(U3A-PA1-Pad15)") (class "Default")
      (node (ref "U3") (pin "15") (pinfunction "PA1_15") (pintype "bidirectional"))
    )
    (net (code "89") (name "unconnected-(U3A-PA4-Pad20)") (class "Default")
      (node (ref "U3") (pin "20") (pinfunction "PA4_20") (pintype "bidirectional"))
    )
    (net (code "90") (name "unconnected-(U3A-PA5-Pad21)") (class "Default")
      (node (ref "U3") (pin "21") (pinfunction "PA5_21") (pintype "bidirectional"))
    )
    (net (code "91") (name "unconnected-(U3A-PA6-Pad22)") (class "Default")
      (node (ref "U3") (pin "22") (pinfunction "PA6_22") (pintype "bidirectional"))
    )
    (net (code "92") (name "unconnected-(U3A-PA7-Pad23)") (class "Default")
      (node (ref "U3") (pin "23") (pinfunction "PA7_23") (pintype "bidirectional"))
    )
    (net (code "93") (name "unconnected-(U3A-PA8-Pad41)") (class "Default")
      (node (ref "U3") (pin "41") (pinfunction "PA8_41") (pintype "bidirectional"))
    )
    (net (code "94") (name "unconnected-(U3A-PA12-Pad45)") (class "Default")
      (node (ref "U3") (pin "45") (pinfunction "PA12_45") (pintype "bidirectional"))
    )
    (net (code "95") (name "unconnected-(U3A-PA15-Pad50)") (class "Default")
      (node (ref "U3") (pin "50") (pinfunction "PA15_50") (pintype "bidirectional"))
    )
    (net (code "96") (name "unconnected-(U3A-PB2-Pad28)") (class "Default")
      (node (ref "U3") (pin "28") (pinfunction "PB2_28") (pintype "bidirectional"))
    )
    (net (code "97") (name "unconnected-(U3A-PB3-Pad55)") (class "Default")
      (node (ref "U3") (pin "55") (pinfunction "PB3_55") (pintype "bidirectional"))
    )
    (net (code "98") (name "unconnected-(U3A-PB4-Pad56)") (class "Default")
      (node (ref "U3") (pin "56") (pinfunction "PB4_56") (pintype "bidirectional"))
    )
    (net (code "99") (name "unconnected-(U3A-PB5-Pad57)") (class "Default")
      (node (ref "U3") (pin "57") (pinfunction "PB5_57") (pintype "bidirectional"))
    )
    (net (code "100") (name "unconnected-(U3A-PB6-Pad58)") (class "Default")
      (node (ref "U3") (pin "58") (pinfunction "PB6_58") (pintype "bidirectional"))
    )
    (net (code "101") (name "unconnected-(U3A-PB7-Pad59)") (class "Default")
      (node (ref "U3") (pin "59") (pinfunction "PB7_59") (pintype "bidirectional"))
    )
    (net (code "102") (name "unconnected-(U3A-PB8-Pad61)") (class "Default")
      (node (ref "U3") (pin "61") (pinfunction "PB8_61") (pintype "bidirectional"))
    )
    (net (code "103") (name "unconnected-(U3A-PB9-Pad62)") (class "Default")
      (node (ref "U3") (pin "62") (pinfunction "PB9_62") (pintype "bidirectional"))
    )
    (net (code "104") (name "unconnected-(U3A-PB10-Pad29)") (class "Default")
      (node (ref "U3") (pin "29") (pinfunction "PB10_29") (pintype "bidirectional"))
    )
    (net (code "105") (name "unconnected-(U3A-PB11-Pad30)") (class "Default")
      (node (ref "U3") (pin "30") (pinfunction "PB11_30") (pintype "bidirectional"))
    )
    (net (code "106") (name "unconnected-(U3A-PC2-Pad10)") (class "Default")
      (node (ref "U3") (pin "10") (pinfunction "PC2_10") (pintype "bidirectional"))
    )
    (net (code "107") (name "unconnected-(U3A-PC3-Pad11)") (class "Default")
      (node (ref "U3") (pin "11") (pinfunction "PC3_11") (pintype "bidirectional"))
    )
    (net (code "108") (name "unconnected-(U3A-PC9-Pad40)") (class "Default")
      (node (ref "U3") (pin "40") (pinfunction "PC9_40") (pintype "bidirectional"))
    )
    (net (code "109") (name "unconnected-(U3A-PC10-Pad51)") (class "Default")
      (node (ref "U3") (pin "51") (pinfunction "PC10_51") (pintype "bidirectional"))
    )
    (net (code "110") (name "unconnected-(U3A-PC13-TAMPER-RTC-Pad2)") (class "Default")
      (node (ref "U3") (pin "2") (pinfunction "PC13-TAMPER-RTC_2") (pintype "bidirectional"))
    )
    (net (code "111") (name "unconnected-(U3A-PC14-OSC32_IN-Pad3)") (class "Default")
      (node (ref "U3") (pin "3") (pinfunction "PC14-OSC32_IN_3") (pintype "bidirectional"))
    )
    (net (code "112") (name "unconnected-(U3A-PC15-OSC32_OUT-Pad4)") (class "Default")
      (node (ref "U3") (pin "4") (pinfunction "PC15-OSC32_OUT_4") (pintype "bidirectional"))
    )
    (net (code "113") (name "unconnected-(U3A-PD2-Pad54)") (class "Default")
      (node (ref "U3") (pin "54") (pinfunction "PD2_54") (pintype "bidirectional"))
    )
    (net (code "114") (name "unconnected-(U3B-VBAT-Pad1)") (class "Default")
      (node (ref "U3") (pin "1") (pinfunction "VBAT_1") (pintype "power_in"))
    )
  )
)
